# SLS_schematic.net
KiCad netlist of a schematic drawn in EAGLE
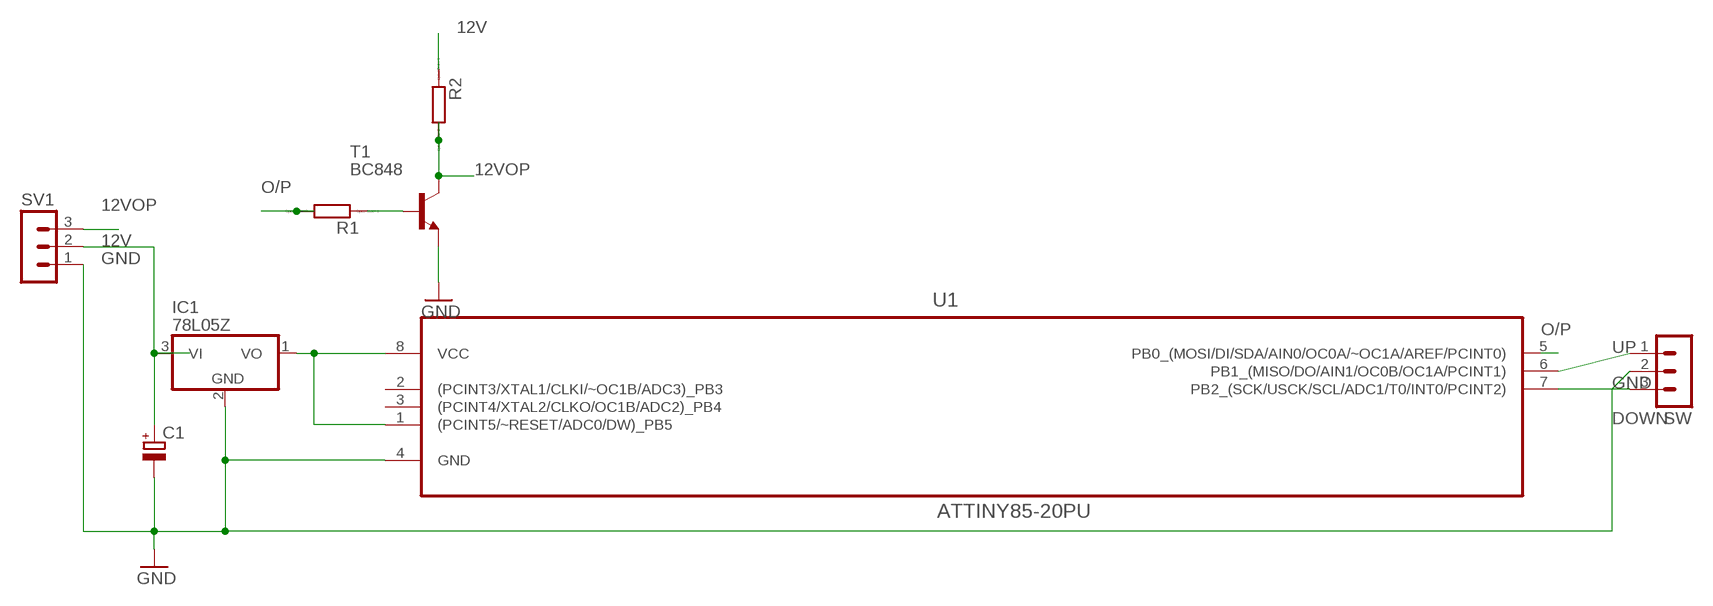
[diagram p0: schematic, sheet 1]

(export (version "E")
  (design (tool "Eeschema 10.0.6"))
  (components
    (comp (ref "C1")
      (value "CPOL-EUCT3216")
      (footprint "eagle-import:CT3216")
      (libsource (lib "eagle-import") (part "CPOL-EUCT3216"))
    )
    (comp (ref "IC1")
      (value "78L05Z")
      (footprint "eagle-import:TO92")
      (libsource (lib "eagle-import") (part "78ZL05"))
    )
    (comp (ref "R1")
      (value "R-EU_R0805")
      (footprint "eagle-import:R0805")
      (libsource (lib "eagle-import") (part "R-EU_R0805"))
    )
    (comp (ref "R2")
      (value "R-EU_R0805")
      (footprint "eagle-import:R0805")
      (libsource (lib "eagle-import") (part "R-EU_R0805"))
    )
    (comp (ref "SV1")
      (value "MA03-1")
      (footprint "eagle-import:MA03-1")
      (libsource (lib "eagle-import") (part "MA03-1"))
    )
    (comp (ref "SW")
      (value "MA03-1")
      (footprint "eagle-import:MA03-1")
      (libsource (lib "eagle-import") (part "MA03-1"))
    )
    (comp (ref "T1")
      (value "BC848")
      (footprint "eagle-import:SOT23")
      (libsource (lib "eagle-import") (part "BC848"))
    )
    (comp (ref "U1")
      (value "ATTINY85-20PU")
      (footprint "eagle-import:DIP254P762X533-8")
      (libsource (lib "eagle-import") (part "ATTINY85-20PU"))
    )
  )
  (nets
    (net (code "1") (name "/12V") (class "Default")
      (node (ref "C1") (pin "+") (pinfunction "+_+") (pintype "passive"))
      (node (ref "IC1") (pin "3") (pinfunction "VI_3") (pintype "input"))
      (node (ref "R2") (pin "1") (pinfunction "1_1") (pintype "passive"))
      (node (ref "SV1") (pin "2") (pinfunction "2_2") (pintype "passive"))
    )
    (net (code "2") (name "/12VOP") (class "Default")
      (node (ref "R2") (pin "2") (pinfunction "2_2") (pintype "passive"))
      (node (ref "SV1") (pin "3") (pinfunction "3_3") (pintype "passive"))
      (node (ref "T1") (pin "3") (pinfunction "C_3") (pintype "passive"))
    )
    (net (code "3") (name "/DOWN") (class "Default")
      (node (ref "SW") (pin "3") (pinfunction "3_3") (pintype "passive"))
      (node (ref "U1") (pin "7") (pinfunction "PB2_(SCK/USCK/SCL/ADC1/T0/INT0/PCINT2)_7") (pintype "bidirectional"))
    )
    (net (code "4") (name "/O{slash}P") (class "Default")
      (node (ref "R1") (pin "2") (pinfunction "2_2") (pintype "passive"))
      (node (ref "U1") (pin "5") (pinfunction "PB0_(MOSI/DI/SDA/AIN0/OC0A/~{OC1A/AREF/PCINT0})_5") (pintype "bidirectional"))
    )
    (net (code "5") (name "/UP") (class "Default")
      (node (ref "SW") (pin "1") (pinfunction "1_1") (pintype "passive"))
      (node (ref "U1") (pin "6") (pinfunction "PB1_(MISO/DO/AIN1/OC0B/OC1A/PCINT1)_6") (pintype "bidirectional"))
    )
    (net (code "6") (name "GND") (class "Default")
      (node (ref "C1") (pin "-") (pinfunction "-_-") (pintype "passive"))
      (node (ref "IC1") (pin "2") (pinfunction "GND_2") (pintype "passive"))
      (node (ref "SV1") (pin "1") (pinfunction "1_1") (pintype "passive"))
      (node (ref "SW") (pin "2") (pinfunction "2_2") (pintype "passive"))
      (node (ref "T1") (pin "2") (pinfunction "E_2") (pintype "passive"))
      (node (ref "U1") (pin "4") (pinfunction "GND_4") (pintype "passive"))
    )
    (net (code "7") (name "Net-(IC1-VO)") (class "Default")
      (node (ref "IC1") (pin "1") (pinfunction "VO_1") (pintype "passive"))
      (node (ref "U1") (pin "1") (pinfunction "(PCINT5/~{RESET/ADC0/DW})_PB5_1") (pintype "bidirectional"))
      (node (ref "U1") (pin "8") (pinfunction "VCC_8") (pintype "power_in"))
    )
    (net (code "8") (name "Net-(T1-B)") (class "Default")
      (node (ref "R1") (pin "1") (pinfunction "1_1") (pintype "passive"))
      (node (ref "T1") (pin "1") (pinfunction "B_1") (pintype "passive"))
    )
    (net (code "9") (name "unconnected-(U1-(PCINT3{slash}XTAL1{slash}CLKI{slash}~{OC1B{slash}ADC3})_PB3-Pad2)") (class "Default")
      (node (ref "U1") (pin "2") (pinfunction "(PCINT3/XTAL1/CLKI/~{OC1B/ADC3})_PB3_2") (pintype "bidirectional"))
    )
    (net (code "10") (name "unconnected-(U1-(PCINT4{slash}XTAL2{slash}CLKO{slash}OC1B{slash}ADC2)_PB4-Pad3)") (class "Default")
      (node (ref "U1") (pin "3") (pinfunction "(PCINT4/XTAL2/CLKO/OC1B/ADC2)_PB4_3") (pintype "bidirectional"))
    )
  )
)
